# Chess_Clock.net
KiCad netlist of a schematic drawn in Altium Designer
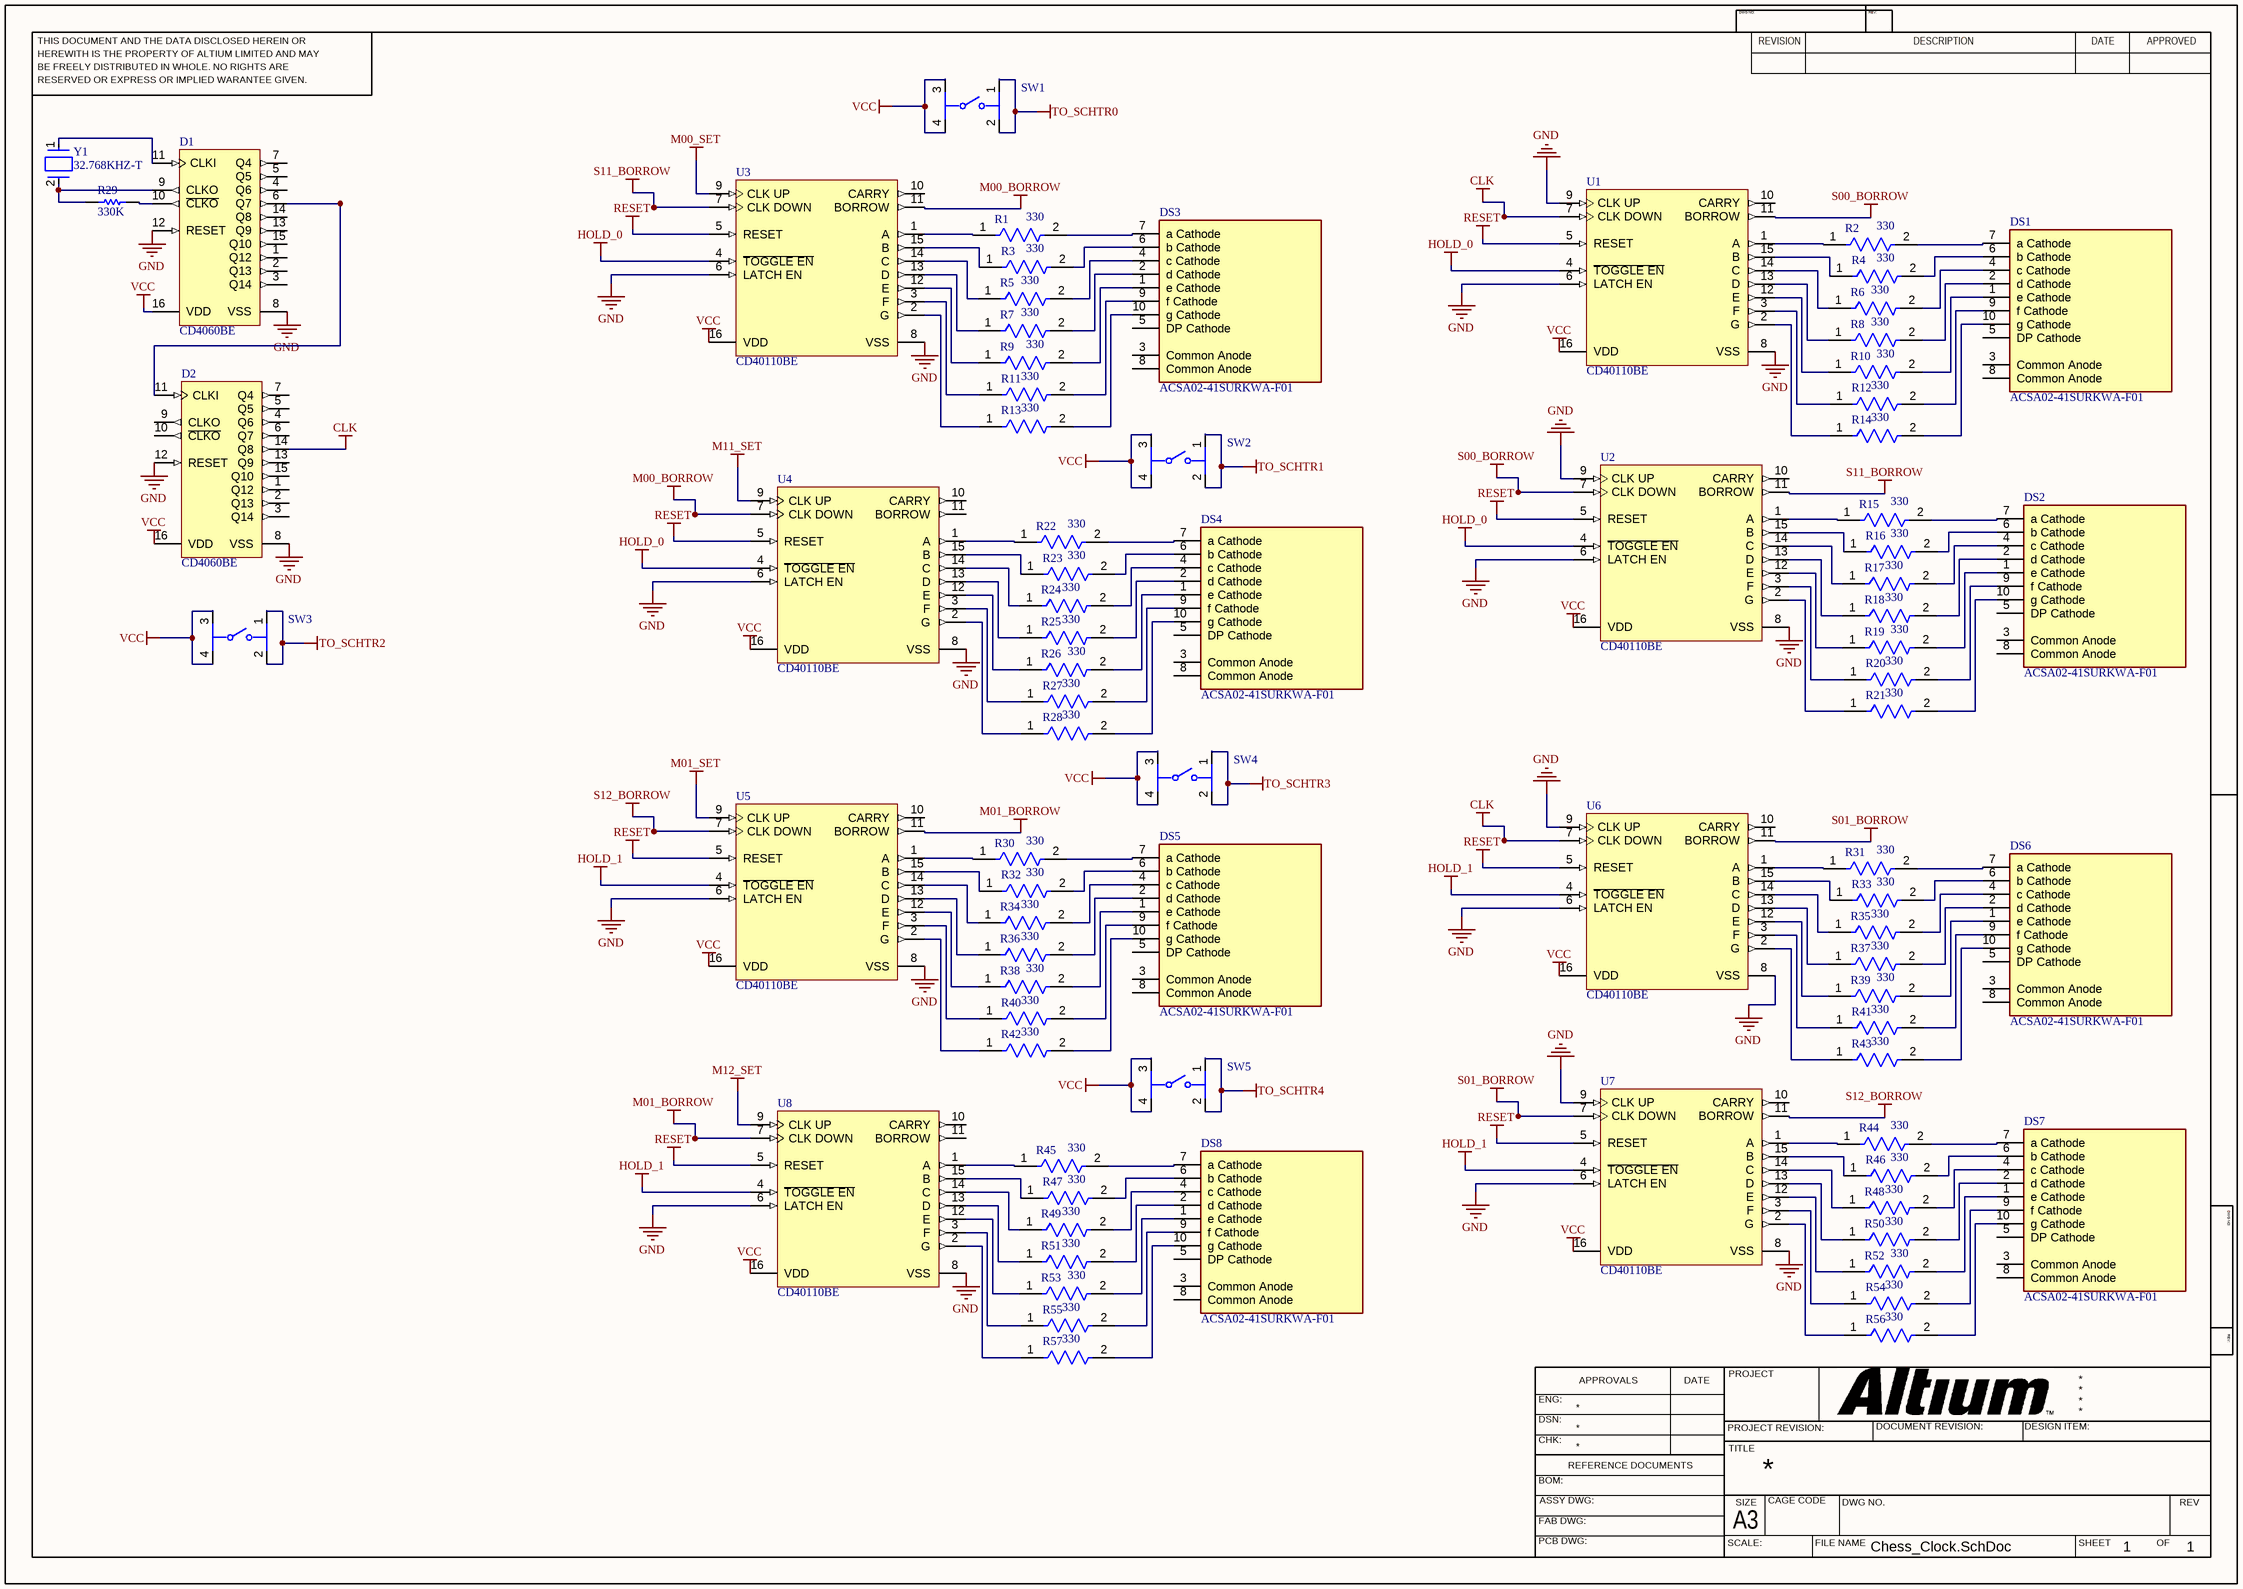
[diagram p0: Chess_Clock.SchDoc]

(export (version "E")
  (design (tool "Eeschema 10.0.6"))
  (components
    (comp (ref "D1")
      (value "CD4060BE")
      (footprint "N0016A")
      (fields (field (name "MANUFACTURER") "Texas Instruments"))
      (libsource (lib "Altium Content Vault") (part "TI-CD4060B-16"))
    )
    (comp (ref "D2")
      (value "CD4060BE")
      (footprint "N0016A")
      (fields (field (name "MANUFACTURER") "Texas Instruments"))
      (libsource (lib "Altium Content Vault") (part "TI-CD4060B-16"))
    )
    (comp (ref "DS1")
      (value "ACSA02-41SURKWA-F01")
      (footprint "FP-ACSA02-41SURKWA-F01-MFG")
      (description "DISPLAY 7-SEG 0.2\" SGL RED 10SMD")
      (libsource (lib "Altium Content Vault") (part "4bb9e92f745044eccd54b42966cc4de"))
    )
    (comp (ref "DS2")
      (value "ACSA02-41SURKWA-F01")
      (footprint "FP-ACSA02-41SURKWA-F01-MFG")
      (description "DISPLAY 7-SEG 0.2\" SGL RED 10SMD")
      (libsource (lib "Altium Content Vault") (part "4bb9e92f745044eccd54b42966cc4de"))
    )
    (comp (ref "DS3")
      (value "ACSA02-41SURKWA-F01")
      (footprint "FP-ACSA02-41SURKWA-F01-MFG")
      (description "DISPLAY 7-SEG 0.2\" SGL RED 10SMD")
      (libsource (lib "Altium Content Vault") (part "4bb9e92f745044eccd54b42966cc4de"))
    )
    (comp (ref "DS4")
      (value "ACSA02-41SURKWA-F01")
      (footprint "FP-ACSA02-41SURKWA-F01-MFG")
      (description "DISPLAY 7-SEG 0.2\" SGL RED 10SMD")
      (libsource (lib "Altium Content Vault") (part "4bb9e92f745044eccd54b42966cc4de"))
    )
    (comp (ref "DS5")
      (value "ACSA02-41SURKWA-F01")
      (footprint "FP-ACSA02-41SURKWA-F01-MFG")
      (description "DISPLAY 7-SEG 0.2\" SGL RED 10SMD")
      (libsource (lib "Altium Content Vault") (part "4bb9e92f745044eccd54b42966cc4de"))
    )
    (comp (ref "DS6")
      (value "ACSA02-41SURKWA-F01")
      (footprint "FP-ACSA02-41SURKWA-F01-MFG")
      (description "DISPLAY 7-SEG 0.2\" SGL RED 10SMD")
      (libsource (lib "Altium Content Vault") (part "4bb9e92f745044eccd54b42966cc4de"))
    )
    (comp (ref "DS7")
      (value "ACSA02-41SURKWA-F01")
      (footprint "FP-ACSA02-41SURKWA-F01-MFG")
      (description "DISPLAY 7-SEG 0.2\" SGL RED 10SMD")
      (libsource (lib "Altium Content Vault") (part "4bb9e92f745044eccd54b42966cc4de"))
    )
    (comp (ref "DS8")
      (value "ACSA02-41SURKWA-F01")
      (footprint "FP-ACSA02-41SURKWA-F01-MFG")
      (description "DISPLAY 7-SEG 0.2\" SGL RED 10SMD")
      (libsource (lib "Altium Content Vault") (part "4bb9e92f745044eccd54b42966cc4de"))
    )
    (comp (ref "R1")
      (value "330")
      (footprint "FP-CRCW0603-e3-MFG")
      (description "RES Thick Film, 330Ω, 1%, 0.1W, 100ppm/°C, 0603")
      (fields (field (name "TOLERANCE") "1%"))
      (libsource (lib "Altium Content Vault") (part "1029c3af85768c4190bb7ad29bc67b5"))
    )
    (comp (ref "R2")
      (value "330")
      (footprint "FP-CRCW0603-e3-MFG")
      (description "RES Thick Film, 330Ω, 1%, 0.1W, 100ppm/°C, 0603")
      (fields (field (name "TOLERANCE") "1%"))
      (libsource (lib "Altium Content Vault") (part "1029c3af85768c4190bb7ad29bc67b5"))
    )
    (comp (ref "R3")
      (value "330")
      (footprint "FP-CRCW0603-e3-MFG")
      (description "RES Thick Film, 330Ω, 1%, 0.1W, 100ppm/°C, 0603")
      (fields (field (name "TOLERANCE") "1%"))
      (libsource (lib "Altium Content Vault") (part "1029c3af85768c4190bb7ad29bc67b5"))
    )
    (comp (ref "R4")
      (value "330")
      (footprint "FP-CRCW0603-e3-MFG")
      (description "RES Thick Film, 330Ω, 1%, 0.1W, 100ppm/°C, 0603")
      (fields (field (name "TOLERANCE") "1%"))
      (libsource (lib "Altium Content Vault") (part "1029c3af85768c4190bb7ad29bc67b5"))
    )
    (comp (ref "R5")
      (value "330")
      (footprint "FP-CRCW0603-e3-MFG")
      (description "RES Thick Film, 330Ω, 1%, 0.1W, 100ppm/°C, 0603")
      (fields (field (name "TOLERANCE") "1%"))
      (libsource (lib "Altium Content Vault") (part "1029c3af85768c4190bb7ad29bc67b5"))
    )
    (comp (ref "R6")
      (value "330")
      (footprint "FP-CRCW0603-e3-MFG")
      (description "RES Thick Film, 330Ω, 1%, 0.1W, 100ppm/°C, 0603")
      (fields (field (name "TOLERANCE") "1%"))
      (libsource (lib "Altium Content Vault") (part "1029c3af85768c4190bb7ad29bc67b5"))
    )
    (comp (ref "R7")
      (value "330")
      (footprint "FP-CRCW0603-e3-MFG")
      (description "RES Thick Film, 330Ω, 1%, 0.1W, 100ppm/°C, 0603")
      (fields (field (name "TOLERANCE") "1%"))
      (libsource (lib "Altium Content Vault") (part "1029c3af85768c4190bb7ad29bc67b5"))
    )
    (comp (ref "R8")
      (value "330")
      (footprint "FP-CRCW0603-e3-MFG")
      (description "RES Thick Film, 330Ω, 1%, 0.1W, 100ppm/°C, 0603")
      (fields (field (name "TOLERANCE") "1%"))
      (libsource (lib "Altium Content Vault") (part "1029c3af85768c4190bb7ad29bc67b5"))
    )
    (comp (ref "R9")
      (value "330")
      (footprint "FP-CRCW0603-e3-MFG")
      (description "RES Thick Film, 330Ω, 1%, 0.1W, 100ppm/°C, 0603")
      (fields (field (name "TOLERANCE") "1%"))
      (libsource (lib "Altium Content Vault") (part "1029c3af85768c4190bb7ad29bc67b5"))
    )
    (comp (ref "R10")
      (value "330")
      (footprint "FP-CRCW0603-e3-MFG")
      (description "RES Thick Film, 330Ω, 1%, 0.1W, 100ppm/°C, 0603")
      (fields (field (name "TOLERANCE") "1%"))
      (libsource (lib "Altium Content Vault") (part "1029c3af85768c4190bb7ad29bc67b5"))
    )
    (comp (ref "R11")
      (value "330")
      (footprint "FP-CRCW0603-e3-MFG")
      (description "RES Thick Film, 330Ω, 1%, 0.1W, 100ppm/°C, 0603")
      (fields (field (name "TOLERANCE") "1%"))
      (libsource (lib "Altium Content Vault") (part "1029c3af85768c4190bb7ad29bc67b5"))
    )
    (comp (ref "R12")
      (value "330")
      (footprint "FP-CRCW0603-e3-MFG")
      (description "RES Thick Film, 330Ω, 1%, 0.1W, 100ppm/°C, 0603")
      (fields (field (name "TOLERANCE") "1%"))
      (libsource (lib "Altium Content Vault") (part "1029c3af85768c4190bb7ad29bc67b5"))
    )
    (comp (ref "R13")
      (value "330")
      (footprint "FP-CRCW0603-e3-MFG")
      (description "RES Thick Film, 330Ω, 1%, 0.1W, 100ppm/°C, 0603")
      (fields (field (name "TOLERANCE") "1%"))
      (libsource (lib "Altium Content Vault") (part "1029c3af85768c4190bb7ad29bc67b5"))
    )
    (comp (ref "R14")
      (value "330")
      (footprint "FP-CRCW0603-e3-MFG")
      (description "RES Thick Film, 330Ω, 1%, 0.1W, 100ppm/°C, 0603")
      (fields (field (name "TOLERANCE") "1%"))
      (libsource (lib "Altium Content Vault") (part "1029c3af85768c4190bb7ad29bc67b5"))
    )
    (comp (ref "R15")
      (value "330")
      (footprint "FP-CRCW0603-e3-MFG")
      (description "RES Thick Film, 330Ω, 1%, 0.1W, 100ppm/°C, 0603")
      (fields (field (name "TOLERANCE") "1%"))
      (libsource (lib "Altium Content Vault") (part "1029c3af85768c4190bb7ad29bc67b5"))
    )
    (comp (ref "R16")
      (value "330")
      (footprint "FP-CRCW0603-e3-MFG")
      (description "RES Thick Film, 330Ω, 1%, 0.1W, 100ppm/°C, 0603")
      (fields (field (name "TOLERANCE") "1%"))
      (libsource (lib "Altium Content Vault") (part "1029c3af85768c4190bb7ad29bc67b5"))
    )
    (comp (ref "R17")
      (value "330")
      (footprint "FP-CRCW0603-e3-MFG")
      (description "RES Thick Film, 330Ω, 1%, 0.1W, 100ppm/°C, 0603")
      (fields (field (name "TOLERANCE") "1%"))
      (libsource (lib "Altium Content Vault") (part "1029c3af85768c4190bb7ad29bc67b5"))
    )
    (comp (ref "R18")
      (value "330")
      (footprint "FP-CRCW0603-e3-MFG")
      (description "RES Thick Film, 330Ω, 1%, 0.1W, 100ppm/°C, 0603")
      (fields (field (name "TOLERANCE") "1%"))
      (libsource (lib "Altium Content Vault") (part "1029c3af85768c4190bb7ad29bc67b5"))
    )
    (comp (ref "R19")
      (value "330")
      (footprint "FP-CRCW0603-e3-MFG")
      (description "RES Thick Film, 330Ω, 1%, 0.1W, 100ppm/°C, 0603")
      (fields (field (name "TOLERANCE") "1%"))
      (libsource (lib "Altium Content Vault") (part "1029c3af85768c4190bb7ad29bc67b5"))
    )
    (comp (ref "R20")
      (value "330")
      (footprint "FP-CRCW0603-e3-MFG")
      (description "RES Thick Film, 330Ω, 1%, 0.1W, 100ppm/°C, 0603")
      (fields (field (name "TOLERANCE") "1%"))
      (libsource (lib "Altium Content Vault") (part "1029c3af85768c4190bb7ad29bc67b5"))
    )
    (comp (ref "R21")
      (value "330")
      (footprint "FP-CRCW0603-e3-MFG")
      (description "RES Thick Film, 330Ω, 1%, 0.1W, 100ppm/°C, 0603")
      (fields (field (name "TOLERANCE") "1%"))
      (libsource (lib "Altium Content Vault") (part "1029c3af85768c4190bb7ad29bc67b5"))
    )
    (comp (ref "R22")
      (value "330")
      (footprint "FP-CRCW0603-e3-MFG")
      (description "RES Thick Film, 330Ω, 1%, 0.1W, 100ppm/°C, 0603")
      (fields (field (name "TOLERANCE") "1%"))
      (libsource (lib "Altium Content Vault") (part "1029c3af85768c4190bb7ad29bc67b5"))
    )
    (comp (ref "R23")
      (value "330")
      (footprint "FP-CRCW0603-e3-MFG")
      (description "RES Thick Film, 330Ω, 1%, 0.1W, 100ppm/°C, 0603")
      (fields (field (name "TOLERANCE") "1%"))
      (libsource (lib "Altium Content Vault") (part "1029c3af85768c4190bb7ad29bc67b5"))
    )
    (comp (ref "R24")
      (value "330")
      (footprint "FP-CRCW0603-e3-MFG")
      (description "RES Thick Film, 330Ω, 1%, 0.1W, 100ppm/°C, 0603")
      (fields (field (name "TOLERANCE") "1%"))
      (libsource (lib "Altium Content Vault") (part "1029c3af85768c4190bb7ad29bc67b5"))
    )
    (comp (ref "R25")
      (value "330")
      (footprint "FP-CRCW0603-e3-MFG")
      (description "RES Thick Film, 330Ω, 1%, 0.1W, 100ppm/°C, 0603")
      (fields (field (name "TOLERANCE") "1%"))
      (libsource (lib "Altium Content Vault") (part "1029c3af85768c4190bb7ad29bc67b5"))
    )
    (comp (ref "R26")
      (value "330")
      (footprint "FP-CRCW0603-e3-MFG")
      (description "RES Thick Film, 330Ω, 1%, 0.1W, 100ppm/°C, 0603")
      (fields (field (name "TOLERANCE") "1%"))
      (libsource (lib "Altium Content Vault") (part "1029c3af85768c4190bb7ad29bc67b5"))
    )
    (comp (ref "R27")
      (value "330")
      (footprint "FP-CRCW0603-e3-MFG")
      (description "RES Thick Film, 330Ω, 1%, 0.1W, 100ppm/°C, 0603")
      (fields (field (name "TOLERANCE") "1%"))
      (libsource (lib "Altium Content Vault") (part "1029c3af85768c4190bb7ad29bc67b5"))
    )
    (comp (ref "R28")
      (value "330")
      (footprint "FP-CRCW0603-e3-MFG")
      (description "RES Thick Film, 330Ω, 1%, 0.1W, 100ppm/°C, 0603")
      (fields (field (name "TOLERANCE") "1%"))
      (libsource (lib "Altium Content Vault") (part "1029c3af85768c4190bb7ad29bc67b5"))
    )
    (comp (ref "R29")
      (value "330K")
      (footprint "RESC1609X50X30NL8T20")
      (description "Chip Resistor, 0 Ohm, Jumper, 100 mW, -55 to 155 degC, 0603 (1608 Metric), RoHS, Tape and Reel")
      (fields (field (name "MANUFACTURER") "Vishay Semiconductor"))
      (libsource (lib "Altium Content Vault") (part "RES-2"))
    )
    (comp (ref "R30")
      (value "330")
      (footprint "FP-CRCW0603-e3-MFG")
      (description "RES Thick Film, 330Ω, 1%, 0.1W, 100ppm/°C, 0603")
      (fields (field (name "TOLERANCE") "1%"))
      (libsource (lib "Altium Content Vault") (part "1029c3af85768c4190bb7ad29bc67b5"))
    )
    (comp (ref "R31")
      (value "330")
      (footprint "FP-CRCW0603-e3-MFG")
      (description "RES Thick Film, 330Ω, 1%, 0.1W, 100ppm/°C, 0603")
      (fields (field (name "TOLERANCE") "1%"))
      (libsource (lib "Altium Content Vault") (part "1029c3af85768c4190bb7ad29bc67b5"))
    )
    (comp (ref "R32")
      (value "330")
      (footprint "FP-CRCW0603-e3-MFG")
      (description "RES Thick Film, 330Ω, 1%, 0.1W, 100ppm/°C, 0603")
      (fields (field (name "TOLERANCE") "1%"))
      (libsource (lib "Altium Content Vault") (part "1029c3af85768c4190bb7ad29bc67b5"))
    )
    (comp (ref "R33")
      (value "330")
      (footprint "FP-CRCW0603-e3-MFG")
      (description "RES Thick Film, 330Ω, 1%, 0.1W, 100ppm/°C, 0603")
      (fields (field (name "TOLERANCE") "1%"))
      (libsource (lib "Altium Content Vault") (part "1029c3af85768c4190bb7ad29bc67b5"))
    )
    (comp (ref "R34")
      (value "330")
      (footprint "FP-CRCW0603-e3-MFG")
      (description "RES Thick Film, 330Ω, 1%, 0.1W, 100ppm/°C, 0603")
      (fields (field (name "TOLERANCE") "1%"))
      (libsource (lib "Altium Content Vault") (part "1029c3af85768c4190bb7ad29bc67b5"))
    )
    (comp (ref "R35")
      (value "330")
      (footprint "FP-CRCW0603-e3-MFG")
      (description "RES Thick Film, 330Ω, 1%, 0.1W, 100ppm/°C, 0603")
      (fields (field (name "TOLERANCE") "1%"))
      (libsource (lib "Altium Content Vault") (part "1029c3af85768c4190bb7ad29bc67b5"))
    )
    (comp (ref "R36")
      (value "330")
      (footprint "FP-CRCW0603-e3-MFG")
      (description "RES Thick Film, 330Ω, 1%, 0.1W, 100ppm/°C, 0603")
      (fields (field (name "TOLERANCE") "1%"))
      (libsource (lib "Altium Content Vault") (part "1029c3af85768c4190bb7ad29bc67b5"))
    )
    (comp (ref "R37")
      (value "330")
      (footprint "FP-CRCW0603-e3-MFG")
      (description "RES Thick Film, 330Ω, 1%, 0.1W, 100ppm/°C, 0603")
      (fields (field (name "TOLERANCE") "1%"))
      (libsource (lib "Altium Content Vault") (part "1029c3af85768c4190bb7ad29bc67b5"))
    )
    (comp (ref "R38")
      (value "330")
      (footprint "FP-CRCW0603-e3-MFG")
      (description "RES Thick Film, 330Ω, 1%, 0.1W, 100ppm/°C, 0603")
      (fields (field (name "TOLERANCE") "1%"))
      (libsource (lib "Altium Content Vault") (part "1029c3af85768c4190bb7ad29bc67b5"))
    )
    (comp (ref "R39")
      (value "330")
      (footprint "FP-CRCW0603-e3-MFG")
      (description "RES Thick Film, 330Ω, 1%, 0.1W, 100ppm/°C, 0603")
      (fields (field (name "TOLERANCE") "1%"))
      (libsource (lib "Altium Content Vault") (part "1029c3af85768c4190bb7ad29bc67b5"))
    )
    (comp (ref "R40")
      (value "330")
      (footprint "FP-CRCW0603-e3-MFG")
      (description "RES Thick Film, 330Ω, 1%, 0.1W, 100ppm/°C, 0603")
      (fields (field (name "TOLERANCE") "1%"))
      (libsource (lib "Altium Content Vault") (part "1029c3af85768c4190bb7ad29bc67b5"))
    )
    (comp (ref "R41")
      (value "330")
      (footprint "FP-CRCW0603-e3-MFG")
      (description "RES Thick Film, 330Ω, 1%, 0.1W, 100ppm/°C, 0603")
      (fields (field (name "TOLERANCE") "1%"))
      (libsource (lib "Altium Content Vault") (part "1029c3af85768c4190bb7ad29bc67b5"))
    )
    (comp (ref "R42")
      (value "330")
      (footprint "FP-CRCW0603-e3-MFG")
      (description "RES Thick Film, 330Ω, 1%, 0.1W, 100ppm/°C, 0603")
      (fields (field (name "TOLERANCE") "1%"))
      (libsource (lib "Altium Content Vault") (part "1029c3af85768c4190bb7ad29bc67b5"))
    )
    (comp (ref "R43")
      (value "330")
      (footprint "FP-CRCW0603-e3-MFG")
      (description "RES Thick Film, 330Ω, 1%, 0.1W, 100ppm/°C, 0603")
      (fields (field (name "TOLERANCE") "1%"))
      (libsource (lib "Altium Content Vault") (part "1029c3af85768c4190bb7ad29bc67b5"))
    )
    (comp (ref "R44")
      (value "330")
      (footprint "FP-CRCW0603-e3-MFG")
      (description "RES Thick Film, 330Ω, 1%, 0.1W, 100ppm/°C, 0603")
      (fields (field (name "TOLERANCE") "1%"))
      (libsource (lib "Altium Content Vault") (part "1029c3af85768c4190bb7ad29bc67b5"))
    )
    (comp (ref "R45")
      (value "330")
      (footprint "FP-CRCW0603-e3-MFG")
      (description "RES Thick Film, 330Ω, 1%, 0.1W, 100ppm/°C, 0603")
      (fields (field (name "TOLERANCE") "1%"))
      (libsource (lib "Altium Content Vault") (part "1029c3af85768c4190bb7ad29bc67b5"))
    )
    (comp (ref "R46")
      (value "330")
      (footprint "FP-CRCW0603-e3-MFG")
      (description "RES Thick Film, 330Ω, 1%, 0.1W, 100ppm/°C, 0603")
      (fields (field (name "TOLERANCE") "1%"))
      (libsource (lib "Altium Content Vault") (part "1029c3af85768c4190bb7ad29bc67b5"))
    )
    (comp (ref "R47")
      (value "330")
      (footprint "FP-CRCW0603-e3-MFG")
      (description "RES Thick Film, 330Ω, 1%, 0.1W, 100ppm/°C, 0603")
      (fields (field (name "TOLERANCE") "1%"))
      (libsource (lib "Altium Content Vault") (part "1029c3af85768c4190bb7ad29bc67b5"))
    )
    (comp (ref "R48")
      (value "330")
      (footprint "FP-CRCW0603-e3-MFG")
      (description "RES Thick Film, 330Ω, 1%, 0.1W, 100ppm/°C, 0603")
      (fields (field (name "TOLERANCE") "1%"))
      (libsource (lib "Altium Content Vault") (part "1029c3af85768c4190bb7ad29bc67b5"))
    )
    (comp (ref "R49")
      (value "330")
      (footprint "FP-CRCW0603-e3-MFG")
      (description "RES Thick Film, 330Ω, 1%, 0.1W, 100ppm/°C, 0603")
      (fields (field (name "TOLERANCE") "1%"))
      (libsource (lib "Altium Content Vault") (part "1029c3af85768c4190bb7ad29bc67b5"))
    )
    (comp (ref "R50")
      (value "330")
      (footprint "FP-CRCW0603-e3-MFG")
      (description "RES Thick Film, 330Ω, 1%, 0.1W, 100ppm/°C, 0603")
      (fields (field (name "TOLERANCE") "1%"))
      (libsource (lib "Altium Content Vault") (part "1029c3af85768c4190bb7ad29bc67b5"))
    )
    (comp (ref "R51")
      (value "330")
      (footprint "FP-CRCW0603-e3-MFG")
      (description "RES Thick Film, 330Ω, 1%, 0.1W, 100ppm/°C, 0603")
      (fields (field (name "TOLERANCE") "1%"))
      (libsource (lib "Altium Content Vault") (part "1029c3af85768c4190bb7ad29bc67b5"))
    )
    (comp (ref "R52")
      (value "330")
      (footprint "FP-CRCW0603-e3-MFG")
      (description "RES Thick Film, 330Ω, 1%, 0.1W, 100ppm/°C, 0603")
      (fields (field (name "TOLERANCE") "1%"))
      (libsource (lib "Altium Content Vault") (part "1029c3af85768c4190bb7ad29bc67b5"))
    )
    (comp (ref "R53")
      (value "330")
      (footprint "FP-CRCW0603-e3-MFG")
      (description "RES Thick Film, 330Ω, 1%, 0.1W, 100ppm/°C, 0603")
      (fields (field (name "TOLERANCE") "1%"))
      (libsource (lib "Altium Content Vault") (part "1029c3af85768c4190bb7ad29bc67b5"))
    )
    (comp (ref "R54")
      (value "330")
      (footprint "FP-CRCW0603-e3-MFG")
      (description "RES Thick Film, 330Ω, 1%, 0.1W, 100ppm/°C, 0603")
      (fields (field (name "TOLERANCE") "1%"))
      (libsource (lib "Altium Content Vault") (part "1029c3af85768c4190bb7ad29bc67b5"))
    )
    (comp (ref "R55")
      (value "330")
      (footprint "FP-CRCW0603-e3-MFG")
      (description "RES Thick Film, 330Ω, 1%, 0.1W, 100ppm/°C, 0603")
      (fields (field (name "TOLERANCE") "1%"))
      (libsource (lib "Altium Content Vault") (part "1029c3af85768c4190bb7ad29bc67b5"))
    )
    (comp (ref "R56")
      (value "330")
      (footprint "FP-CRCW0603-e3-MFG")
      (description "RES Thick Film, 330Ω, 1%, 0.1W, 100ppm/°C, 0603")
      (fields (field (name "TOLERANCE") "1%"))
      (libsource (lib "Altium Content Vault") (part "1029c3af85768c4190bb7ad29bc67b5"))
    )
    (comp (ref "R57")
      (value "330")
      (footprint "FP-CRCW0603-e3-MFG")
      (description "RES Thick Film, 330Ω, 1%, 0.1W, 100ppm/°C, 0603")
      (fields (field (name "TOLERANCE") "1%"))
      (libsource (lib "Altium Content Vault") (part "1029c3af85768c4190bb7ad29bc67b5"))
    )
    (comp (ref "SW1")
      (value "~")
      (footprint "FP-PTS645SM43SMTR92LFS-MFG")
      (description "SWITCH TACTILE SPST-NO 0.05A 12V")
      (libsource (lib "Altium Content Vault") (part "1adf0dd01260c80cf25a44bfd6b99ba"))
    )
    (comp (ref "SW2")
      (value "~")
      (footprint "FP-PTS645SM43SMTR92LFS-MFG")
      (description "SWITCH TACTILE SPST-NO 0.05A 12V")
      (libsource (lib "Altium Content Vault") (part "1adf0dd01260c80cf25a44bfd6b99ba"))
    )
    (comp (ref "SW3")
      (value "~")
      (footprint "FP-PTS645SM43SMTR92LFS-MFG")
      (description "SWITCH TACTILE SPST-NO 0.05A 12V")
      (libsource (lib "Altium Content Vault") (part "1adf0dd01260c80cf25a44bfd6b99ba"))
    )
    (comp (ref "SW4")
      (value "~")
      (footprint "FP-PTS645SM43SMTR92LFS-MFG")
      (description "SWITCH TACTILE SPST-NO 0.05A 12V")
      (libsource (lib "Altium Content Vault") (part "1adf0dd01260c80cf25a44bfd6b99ba"))
    )
    (comp (ref "SW5")
      (value "~")
      (footprint "FP-PTS645SM43SMTR92LFS-MFG")
      (description "SWITCH TACTILE SPST-NO 0.05A 12V")
      (libsource (lib "Altium Content Vault") (part "1adf0dd01260c80cf25a44bfd6b99ba"))
    )
    (comp (ref "U1")
      (value "CD40110BE")
      (footprint "N0016A")
      (description "CMOS Decade Up-Down Counter/Latch/Display Driver, N0016A, TUBE")
      (fields
        (field (name "GENERIC PART NUMBER") "CD40110B")
        (field (name "MANUFACTURER") "Texas Instruments")
      )
      (libsource (lib "Altium Content Vault") (part "TI-CD40110B-N0016A-16"))
    )
    (comp (ref "U2")
      (value "CD40110BE")
      (footprint "N0016A")
      (description "CMOS Decade Up-Down Counter/Latch/Display Driver, N0016A, TUBE")
      (fields
        (field (name "GENERIC PART NUMBER") "CD40110B")
        (field (name "MANUFACTURER") "Texas Instruments")
      )
      (libsource (lib "Altium Content Vault") (part "TI-CD40110B-N0016A-16"))
    )
    (comp (ref "U3")
      (value "CD40110BE")
      (footprint "N0016A")
      (description "CMOS Decade Up-Down Counter/Latch/Display Driver, N0016A, TUBE")
      (fields
        (field (name "GENERIC PART NUMBER") "CD40110B")
        (field (name "MANUFACTURER") "Texas Instruments")
      )
      (libsource (lib "Altium Content Vault") (part "TI-CD40110B-N0016A-16"))
    )
    (comp (ref "U4")
      (value "CD40110BE")
      (footprint "N0016A")
      (description "CMOS Decade Up-Down Counter/Latch/Display Driver, N0016A, TUBE")
      (fields
        (field (name "GENERIC PART NUMBER") "CD40110B")
        (field (name "MANUFACTURER") "Texas Instruments")
      )
      (libsource (lib "Altium Content Vault") (part "TI-CD40110B-N0016A-16"))
    )
    (comp (ref "U5")
      (value "CD40110BE")
      (footprint "N0016A")
      (description "CMOS Decade Up-Down Counter/Latch/Display Driver, N0016A, TUBE")
      (fields
        (field (name "GENERIC PART NUMBER") "CD40110B")
        (field (name "MANUFACTURER") "Texas Instruments")
      )
      (libsource (lib "Altium Content Vault") (part "TI-CD40110B-N0016A-16"))
    )
    (comp (ref "U6")
      (value "CD40110BE")
      (footprint "N0016A")
      (description "CMOS Decade Up-Down Counter/Latch/Display Driver, N0016A, TUBE")
      (fields
        (field (name "GENERIC PART NUMBER") "CD40110B")
        (field (name "MANUFACTURER") "Texas Instruments")
      )
      (libsource (lib "Altium Content Vault") (part "TI-CD40110B-N0016A-16"))
    )
    (comp (ref "U7")
      (value "CD40110BE")
      (footprint "N0016A")
      (description "CMOS Decade Up-Down Counter/Latch/Display Driver, N0016A, TUBE")
      (fields
        (field (name "GENERIC PART NUMBER") "CD40110B")
        (field (name "MANUFACTURER") "Texas Instruments")
      )
      (libsource (lib "Altium Content Vault") (part "TI-CD40110B-N0016A-16"))
    )
    (comp (ref "U8")
      (value "CD40110BE")
      (footprint "N0016A")
      (description "CMOS Decade Up-Down Counter/Latch/Display Driver, N0016A, TUBE")
      (fields
        (field (name "GENERIC PART NUMBER") "CD40110B")
        (field (name "MANUFACTURER") "Texas Instruments")
      )
      (libsource (lib "Altium Content Vault") (part "TI-CD40110B-N0016A-16"))
    )
    (comp (ref "Y1")
      (value "32.768KHZ-T")
      (footprint "FP-AB26TRB-MFG")
      (description "CRYSTAL 32.7680KHZ 12.5PF TH")
      (fields (field (name "TOLERANCE") "20ppm"))
      (libsource (lib "Altium Content Vault") (part "c23a69dc6c9e2f18f2079038eb95dd1"))
    )
  )
  (nets
    (net (code "1") (name "CLK") (class "Default")
      (node (ref "D2") (pin "14") (pinfunction "Q8_14") (pintype "output"))
      (node (ref "U1") (pin "7") (pinfunction "CLK_DOWN_7") (pintype "input"))
      (node (ref "U6") (pin "7") (pinfunction "CLK_DOWN_7") (pintype "input"))
    )
    (net (code "2") (name "GND") (class "Default")
      (node (ref "D1") (pin "12") (pinfunction "RESET_12") (pintype "input"))
      (node (ref "D1") (pin "8") (pinfunction "VSS_8") (pintype "power_in"))
      (node (ref "D2") (pin "12") (pinfunction "RESET_12") (pintype "input"))
      (node (ref "D2") (pin "8") (pinfunction "VSS_8") (pintype "power_in"))
      (node (ref "U1") (pin "6") (pinfunction "LATCH_EN_6") (pintype "input"))
      (node (ref "U1") (pin "8") (pinfunction "VSS_8") (pintype "power_in"))
      (node (ref "U1") (pin "9") (pinfunction "CLK_UP_9") (pintype "input"))
      (node (ref "U2") (pin "6") (pinfunction "LATCH_EN_6") (pintype "input"))
      (node (ref "U2") (pin "8") (pinfunction "VSS_8") (pintype "power_in"))
      (node (ref "U2") (pin "9") (pinfunction "CLK_UP_9") (pintype "input"))
      (node (ref "U3") (pin "6") (pinfunction "LATCH_EN_6") (pintype "input"))
      (node (ref "U3") (pin "8") (pinfunction "VSS_8") (pintype "power_in"))
      (node (ref "U4") (pin "6") (pinfunction "LATCH_EN_6") (pintype "input"))
      (node (ref "U4") (pin "8") (pinfunction "VSS_8") (pintype "power_in"))
      (node (ref "U5") (pin "6") (pinfunction "LATCH_EN_6") (pintype "input"))
      (node (ref "U5") (pin "8") (pinfunction "VSS_8") (pintype "power_in"))
      (node (ref "U6") (pin "6") (pinfunction "LATCH_EN_6") (pintype "input"))
      (node (ref "U6") (pin "8") (pinfunction "VSS_8") (pintype "power_in"))
      (node (ref "U6") (pin "9") (pinfunction "CLK_UP_9") (pintype "input"))
      (node (ref "U7") (pin "6") (pinfunction "LATCH_EN_6") (pintype "input"))
      (node (ref "U7") (pin "8") (pinfunction "VSS_8") (pintype "power_in"))
      (node (ref "U7") (pin "9") (pinfunction "CLK_UP_9") (pintype "input"))
      (node (ref "U8") (pin "6") (pinfunction "LATCH_EN_6") (pintype "input"))
      (node (ref "U8") (pin "8") (pinfunction "VSS_8") (pintype "power_in"))
    )
    (net (code "3") (name "HOLD_0") (class "Default")
      (node (ref "U1") (pin "4") (pinfunction "~{TOGGLE_EN}_4") (pintype "input"))
      (node (ref "U2") (pin "4") (pinfunction "~{TOGGLE_EN}_4") (pintype "input"))
      (node (ref "U3") (pin "4") (pinfunction "~{TOGGLE_EN}_4") (pintype "input"))
      (node (ref "U4") (pin "4") (pinfunction "~{TOGGLE_EN}_4") (pintype "input"))
    )
    (net (code "4") (name "HOLD_1") (class "Default")
      (node (ref "U5") (pin "4") (pinfunction "~{TOGGLE_EN}_4") (pintype "input"))
      (node (ref "U6") (pin "4") (pinfunction "~{TOGGLE_EN}_4") (pintype "input"))
      (node (ref "U7") (pin "4") (pinfunction "~{TOGGLE_EN}_4") (pintype "input"))
      (node (ref "U8") (pin "4") (pinfunction "~{TOGGLE_EN}_4") (pintype "input"))
    )
    (net (code "5") (name "M00_BORROW") (class "Default")
      (node (ref "U3") (pin "11") (pinfunction "BORROW_11") (pintype "output"))
      (node (ref "U4") (pin "7") (pinfunction "CLK_DOWN_7") (pintype "input"))
    )
    (net (code "6") (name "M00_SET") (class "Default")
      (node (ref "U3") (pin "9") (pinfunction "CLK_UP_9") (pintype "input"))
    )
    (net (code "7") (name "M01_BORROW") (class "Default")
      (node (ref "U5") (pin "11") (pinfunction "BORROW_11") (pintype "output"))
      (node (ref "U8") (pin "7") (pinfunction "CLK_DOWN_7") (pintype "input"))
    )
    (net (code "8") (name "M01_SET") (class "Default")
      (node (ref "U5") (pin "9") (pinfunction "CLK_UP_9") (pintype "input"))
    )
    (net (code "9") (name "M11_SET") (class "Default")
      (node (ref "U4") (pin "9") (pinfunction "CLK_UP_9") (pintype "input"))
    )
    (net (code "10") (name "M12_SET") (class "Default")
      (node (ref "U8") (pin "9") (pinfunction "CLK_UP_9") (pintype "input"))
    )
    (net (code "11") (name "Net-(D1-CLKI)") (class "Default")
      (node (ref "D1") (pin "11") (pinfunction "CLKI_11") (pintype "input"))
      (node (ref "Y1") (pin "1") (pinfunction "1_1") (pintype "passive"))
    )
    (net (code "12") (name "Net-(D1-CLKO)") (class "Default")
      (node (ref "D1") (pin "9") (pinfunction "CLKO_9") (pintype "output"))
      (node (ref "R29") (pin "1") (pinfunction "1_1") (pintype "passive"))
      (node (ref "Y1") (pin "2") (pinfunction "2_2") (pintype "passive"))
    )
    (net (code "13") (name "Net-(D1-Q7)") (class "Default")
      (node (ref "D1") (pin "6") (pinfunction "Q7_6") (pintype "output"))
      (node (ref "D2") (pin "11") (pinfunction "CLKI_11") (pintype "input"))
    )
    (net (code "14") (name "Net-(D1-~{CLKO})") (class "Default")
      (node (ref "D1") (pin "10") (pinfunction "~{CLKO}_10") (pintype "output"))
      (node (ref "R29") (pin "2") (pinfunction "2_2") (pintype "passive"))
    )
    (net (code "15") (name "Net-(DS1-a_Cathode)") (class "Default")
      (node (ref "DS1") (pin "7") (pinfunction "a_Cathode_7") (pintype "passive"))
      (node (ref "R2") (pin "2") (pinfunction "2_2") (pintype "passive"))
    )
    (net (code "16") (name "Net-(DS1-b_Cathode)") (class "Default")
      (node (ref "DS1") (pin "6") (pinfunction "b_Cathode_6") (pintype "passive"))
      (node (ref "R4") (pin "2") (pinfunction "2_2") (pintype "passive"))
    )
    (net (code "17") (name "Net-(DS1-c_Cathode)") (class "Default")
      (node (ref "DS1") (pin "4") (pinfunction "c_Cathode_4") (pintype "passive"))
      (node (ref "R6") (pin "2") (pinfunction "2_2") (pintype "passive"))
    )
    (net (code "18") (name "Net-(DS1-d_Cathode)") (class "Default")
      (node (ref "DS1") (pin "2") (pinfunction "d_Cathode_2") (pintype "passive"))
      (node (ref "R8") (pin "2") (pinfunction "2_2") (pintype "passive"))
    )
    (net (code "19") (name "Net-(DS1-e_Cathode)") (class "Default")
      (node (ref "DS1") (pin "1") (pinfunction "e_Cathode_1") (pintype "passive"))
      (node (ref "R10") (pin "2") (pinfunction "2_2") (pintype "passive"))
    )
    (net (code "20") (name "Net-(DS1-f_Cathode)") (class "Default")
      (node (ref "DS1") (pin "9") (pinfunction "f_Cathode_9") (pintype "passive"))
      (node (ref "R12") (pin "2") (pinfunction "2_2") (pintype "passive"))
    )
    (net (code "21") (name "Net-(DS1-g_Cathode)") (class "Default")
      (node (ref "DS1") (pin "10") (pinfunction "g_Cathode_10") (pintype "passive"))
      (node (ref "R14") (pin "2") (pinfunction "2_2") (pintype "passive"))
    )
    (net (code "22") (name "Net-(DS2-a_Cathode)") (class "Default")
      (node (ref "DS2") (pin "7") (pinfunction "a_Cathode_7") (pintype "passive"))
      (node (ref "R15") (pin "2") (pinfunction "2_2") (pintype "passive"))
    )
    (net (code "23") (name "Net-(DS2-b_Cathode)") (class "Default")
      (node (ref "DS2") (pin "6") (pinfunction "b_Cathode_6") (pintype "passive"))
      (node (ref "R16") (pin "2") (pinfunction "2_2") (pintype "passive"))
    )
    (net (code "24") (name "Net-(DS2-c_Cathode)") (class "Default")
      (node (ref "DS2") (pin "4") (pinfunction "c_Cathode_4") (pintype "passive"))
      (node (ref "R17") (pin "2") (pinfunction "2_2") (pintype "passive"))
    )
    (net (code "25") (name "Net-(DS2-d_Cathode)") (class "Default")
      (node (ref "DS2") (pin "2") (pinfunction "d_Cathode_2") (pintype "passive"))
      (node (ref "R18") (pin "2") (pinfunction "2_2") (pintype "passive"))
    )
    (net (code "26") (name "Net-(DS2-e_Cathode)") (class "Default")
      (node (ref "DS2") (pin "1") (pinfunction "e_Cathode_1") (pintype "passive"))
      (node (ref "R19") (pin "2") (pinfunction "2_2") (pintype "passive"))
    )
    (net (code "27") (name "Net-(DS2-f_Cathode)") (class "Default")
      (node (ref "DS2") (pin "9") (pinfunction "f_Cathode_9") (pintype "passive"))
      (node (ref "R20") (pin "2") (pinfunction "2_2") (pintype "passive"))
    )
    (net (code "28") (name "Net-(DS2-g_Cathode)") (class "Default")
      (node (ref "DS2") (pin "10") (pinfunction "g_Cathode_10") (pintype "passive"))
      (node (ref "R21") (pin "2") (pinfunction "2_2") (pintype "passive"))
    )
    (net (code "29") (name "Net-(DS3-a_Cathode)") (class "Default")
      (node (ref "DS3") (pin "7") (pinfunction "a_Cathode_7") (pintype "passive"))
      (node (ref "R1") (pin "2") (pinfunction "2_2") (pintype "passive"))
    )
    (net (code "30") (name "Net-(DS3-b_Cathode)") (class "Default")
      (node (ref "DS3") (pin "6") (pinfunction "b_Cathode_6") (pintype "passive"))
      (node (ref "R3") (pin "2") (pinfunction "2_2") (pintype "passive"))
    )
    (net (code "31") (name "Net-(DS3-c_Cathode)") (class "Default")
      (node (ref "DS3") (pin "4") (pinfunction "c_Cathode_4") (pintype "passive"))
      (node (ref "R5") (pin "2") (pinfunction "2_2") (pintype "passive"))
    )
    (net (code "32") (name "Net-(DS3-d_Cathode)") (class "Default")
      (node (ref "DS3") (pin "2") (pinfunction "d_Cathode_2") (pintype "passive"))
      (node (ref "R7") (pin "2") (pinfunction "2_2") (pintype "passive"))
    )
    (net (code "33") (name "Net-(DS3-e_Cathode)") (class "Default")
      (node (ref "DS3") (pin "1") (pinfunction "e_Cathode_1") (pintype "passive"))
      (node (ref "R9") (pin "2") (pinfunction "2_2") (pintype "passive"))
    )
    (net (code "34") (name "Net-(DS3-f_Cathode)") (class "Default")
      (node (ref "DS3") (pin "9") (pinfunction "f_Cathode_9") (pintype "passive"))
      (node (ref "R11") (pin "2") (pinfunction "2_2") (pintype "passive"))
    )
    (net (code "35") (name "Net-(DS3-g_Cathode)") (class "Default")
      (node (ref "DS3") (pin "10") (pinfunction "g_Cathode_10") (pintype "passive"))
      (node (ref "R13") (pin "2") (pinfunction "2_2") (pintype "passive"))
    )
    (net (code "36") (name "Net-(DS4-a_Cathode)") (class "Default")
      (node (ref "DS4") (pin "7") (pinfunction "a_Cathode_7") (pintype "passive"))
      (node (ref "R22") (pin "2") (pinfunction "2_2") (pintype "passive"))
    )
    (net (code "37") (name "Net-(DS4-b_Cathode)") (class "Default")
      (node (ref "DS4") (pin "6") (pinfunction "b_Cathode_6") (pintype "passive"))
      (node (ref "R23") (pin "2") (pinfunction "2_2") (pintype "passive"))
    )
    (net (code "38") (name "Net-(DS4-c_Cathode)") (class "Default")
      (node (ref "DS4") (pin "4") (pinfunction "c_Cathode_4") (pintype "passive"))
      (node (ref "R24") (pin "2") (pinfunction "2_2") (pintype "passive"))
    )
    (net (code "39") (name "Net-(DS4-d_Cathode)") (class "Default")
      (node (ref "DS4") (pin "2") (pinfunction "d_Cathode_2") (pintype "passive"))
      (node (ref "R25") (pin "2") (pinfunction "2_2") (pintype "passive"))
    )
    (net (code "40") (name "Net-(DS4-e_Cathode)") (class "Default")
      (node (ref "DS4") (pin "1") (pinfunction "e_Cathode_1") (pintype "passive"))
      (node (ref "R26") (pin "2") (pinfunction "2_2") (pintype "passive"))
    )
    (net (code "41") (name "Net-(DS4-f_Cathode)") (class "Default")
      (node (ref "DS4") (pin "9") (pinfunction "f_Cathode_9") (pintype "passive"))
      (node (ref "R27") (pin "2") (pinfunction "2_2") (pintype "passive"))
    )
    (net (code "42") (name "Net-(DS4-g_Cathode)") (class "Default")
      (node (ref "DS4") (pin "10") (pinfunction "g_Cathode_10") (pintype "passive"))
      (node (ref "R28") (pin "2") (pinfunction "2_2") (pintype "passive"))
    )
    (net (code "43") (name "Net-(DS5-a_Cathode)") (class "Default")
      (node (ref "DS5") (pin "7") (pinfunction "a_Cathode_7") (pintype "passive"))
      (node (ref "R30") (pin "2") (pinfunction "2_2") (pintype "passive"))
    )
    (net (code "44") (name "Net-(DS5-b_Cathode)") (class "Default")
      (node (ref "DS5") (pin "6") (pinfunction "b_Cathode_6") (pintype "passive"))
      (node (ref "R32") (pin "2") (pinfunction "2_2") (pintype "passive"))
    )
    (net (code "45") (name "Net-(DS5-c_Cathode)") (class "Default")
      (node (ref "DS5") (pin "4") (pinfunction "c_Cathode_4") (pintype "passive"))
      (node (ref "R34") (pin "2") (pinfunction "2_2") (pintype "passive"))
    )
    (net (code "46") (name "Net-(DS5-d_Cathode)") (class "Default")
      (node (ref "DS5") (pin "2") (pinfunction "d_Cathode_2") (pintype "passive"))
      (node (ref "R36") (pin "2") (pinfunction "2_2") (pintype "passive"))
    )
    (net (code "47") (name "Net-(DS5-e_Cathode)") (class "Default")
      (node (ref "DS5") (pin "1") (pinfunction "e_Cathode_1") (pintype "passive"))
      (node (ref "R38") (pin "2") (pinfunction "2_2") (pintype "passive"))
    )
    (net (code "48") (name "Net-(DS5-f_Cathode)") (class "Default")
      (node (ref "DS5") (pin "9") (pinfunction "f_Cathode_9") (pintype "passive"))
      (node (ref "R40") (pin "2") (pinfunction "2_2") (pintype "passive"))
    )
    (net (code "49") (name "Net-(DS5-g_Cathode)") (class "Default")
      (node (ref "DS5") (pin "10") (pinfunction "g_Cathode_10") (pintype "passive"))
      (node (ref "R42") (pin "2") (pinfunction "2_2") (pintype "passive"))
    )
    (net (code "50") (name "Net-(DS6-a_Cathode)") (class "Default")
      (node (ref "DS6") (pin "7") (pinfunction "a_Cathode_7") (pintype "passive"))
      (node (ref "R31") (pin "2") (pinfunction "2_2") (pintype "passive"))
    )
    (net (code "51") (name "Net-(DS6-b_Cathode)") (class "Default")
      (node (ref "DS6") (pin "6") (pinfunction "b_Cathode_6") (pintype "passive"))
      (node (ref "R33") (pin "2") (pinfunction "2_2") (pintype "passive"))
    )
    (net (code "52") (name "Net-(DS6-c_Cathode)") (class "Default")
      (node (ref "DS6") (pin "4") (pinfunction "c_Cathode_4") (pintype "passive"))
      (node (ref "R35") (pin "2") (pinfunction "2_2") (pintype "passive"))
    )
    (net (code "53") (name "Net-(DS6-d_Cathode)") (class "Default")
      (node (ref "DS6") (pin "2") (pinfunction "d_Cathode_2") (pintype "passive"))
      (node (ref "R37") (pin "2") (pinfunction "2_2") (pintype "passive"))
    )
    (net (code "54") (name "Net-(DS6-e_Cathode)") (class "Default")
      (node (ref "DS6") (pin "1") (pinfunction "e_Cathode_1") (pintype "passive"))
      (node (ref "R39") (pin "2") (pinfunction "2_2") (pintype "passive"))
    )
    (net (code "55") (name "Net-(DS6-f_Cathode)") (class "Default")
      (node (ref "DS6") (pin "9") (pinfunction "f_Cathode_9") (pintype "passive"))
      (node (ref "R41") (pin "2") (pinfunction "2_2") (pintype "passive"))
    )
    (net (code "56") (name "Net-(DS6-g_Cathode)") (class "Default")
      (node (ref "DS6") (pin "10") (pinfunction "g_Cathode_10") (pintype "passive"))
      (node (ref "R43") (pin "2") (pinfunction "2_2") (pintype "passive"))
    )
    (net (code "57") (name "Net-(DS7-a_Cathode)") (class "Default")
      (node (ref "DS7") (pin "7") (pinfunction "a_Cathode_7") (pintype "passive"))
      (node (ref "R44") (pin "2") (pinfunction "2_2") (pintype "passive"))
    )
    (net (code "58") (name "Net-(DS7-b_Cathode)") (class "Default")
      (node (ref "DS7") (pin "6") (pinfunction "b_Cathode_6") (pintype "passive"))
      (node (ref "R46") (pin "2") (pinfunction "2_2") (pintype "passive"))
    )
    (net (code "59") (name "Net-(DS7-c_Cathode)") (class "Default")
      (node (ref "DS7") (pin "4") (pinfunction "c_Cathode_4") (pintype "passive"))
      (node (ref "R48") (pin "2") (pinfunction "2_2") (pintype "passive"))
    )
    (net (code "60") (name "Net-(DS7-d_Cathode)") (class "Default")
      (node (ref "DS7") (pin "2") (pinfunction "d_Cathode_2") (pintype "passive"))
      (node (ref "R50") (pin "2") (pinfunction "2_2") (pintype "passive"))
    )
    (net (code "61") (name "Net-(DS7-e_Cathode)") (class "Default")
      (node (ref "DS7") (pin "1") (pinfunction "e_Cathode_1") (pintype "passive"))
      (node (ref "R52") (pin "2") (pinfunction "2_2") (pintype "passive"))
    )
    (net (code "62") (name "Net-(DS7-f_Cathode)") (class "Default")
      (node (ref "DS7") (pin "9") (pinfunction "f_Cathode_9") (pintype "passive"))
      (node (ref "R54") (pin "2") (pinfunction "2_2") (pintype "passive"))
    )
    (net (code "63") (name "Net-(DS7-g_Cathode)") (class "Default")
      (node (ref "DS7") (pin "10") (pinfunction "g_Cathode_10") (pintype "passive"))
      (node (ref "R56") (pin "2") (pinfunction "2_2") (pintype "passive"))
    )
    (net (code "64") (name "Net-(DS8-a_Cathode)") (class "Default")
      (node (ref "DS8") (pin "7") (pinfunction "a_Cathode_7") (pintype "passive"))
      (node (ref "R45") (pin "2") (pinfunction "2_2") (pintype "passive"))
    )
    (net (code "65") (name "Net-(DS8-b_Cathode)") (class "Default")
      (node (ref "DS8") (pin "6") (pinfunction "b_Cathode_6") (pintype "passive"))
      (node (ref "R47") (pin "2") (pinfunction "2_2") (pintype "passive"))
    )
    (net (code "66") (name "Net-(DS8-c_Cathode)") (class "Default")
      (node (ref "DS8") (pin "4") (pinfunction "c_Cathode_4") (pintype "passive"))
      (node (ref "R49") (pin "2") (pinfunction "2_2") (pintype "passive"))
    )
    (net (code "67") (name "Net-(DS8-d_Cathode)") (class "Default")
      (node (ref "DS8") (pin "2") (pinfunction "d_Cathode_2") (pintype "passive"))
      (node (ref "R51") (pin "2") (pinfunction "2_2") (pintype "passive"))
    )
    (net (code "68") (name "Net-(DS8-e_Cathode)") (class "Default")
      (node (ref "DS8") (pin "1") (pinfunction "e_Cathode_1") (pintype "passive"))
      (node (ref "R53") (pin "2") (pinfunction "2_2") (pintype "passive"))
    )
    (net (code "69") (name "Net-(DS8-f_Cathode)") (class "Default")
      (node (ref "DS8") (pin "9") (pinfunction "f_Cathode_9") (pintype "passive"))
      (node (ref "R55") (pin "2") (pinfunction "2_2") (pintype "passive"))
    )
    (net (code "70") (name "Net-(DS8-g_Cathode)") (class "Default")
      (node (ref "DS8") (pin "10") (pinfunction "g_Cathode_10") (pintype "passive"))
      (node (ref "R57") (pin "2") (pinfunction "2_2") (pintype "passive"))
    )
    (net (code "71") (name "Net-(U1-A)") (class "Default")
      (node (ref "R2") (pin "1") (pinfunction "1_1") (pintype "passive"))
      (node (ref "U1") (pin "1") (pinfunction "A_1") (pintype "output"))
    )
    (net (code "72") (name "Net-(U1-B)") (class "Default")
      (node (ref "R4") (pin "1") (pinfunction "1_1") (pintype "passive"))
      (node (ref "U1") (pin "15") (pinfunction "B_15") (pintype "output"))
    )
    (net (code "73") (name "Net-(U1-C)") (class "Default")
      (node (ref "R6") (pin "1") (pinfunction "1_1") (pintype "passive"))
      (node (ref "U1") (pin "14") (pinfunction "C_14") (pintype "output"))
    )
    (net (code "74") (name "Net-(U1-D)") (class "Default")
      (node (ref "R8") (pin "1") (pinfunction "1_1") (pintype "passive"))
      (node (ref "U1") (pin "13") (pinfunction "D_13") (pintype "output"))
    )
    (net (code "75") (name "Net-(U1-E)") (class "Default")
      (node (ref "R10") (pin "1") (pinfunction "1_1") (pintype "passive"))
      (node (ref "U1") (pin "12") (pinfunction "E_12") (pintype "output"))
    )
    (net (code "76") (name "Net-(U1-F)") (class "Default")
      (node (ref "R12") (pin "1") (pinfunction "1_1") (pintype "passive"))
      (node (ref "U1") (pin "3") (pinfunction "F_3") (pintype "output"))
    )
    (net (code "77") (name "Net-(U1-G)") (class "Default")
      (node (ref "R14") (pin "1") (pinfunction "1_1") (pintype "passive"))
      (node (ref "U1") (pin "2") (pinfunction "G_2") (pintype "output"))
    )
    (net (code "78") (name "Net-(U2-A)") (class "Default")
      (node (ref "R15") (pin "1") (pinfunction "1_1") (pintype "passive"))
      (node (ref "U2") (pin "1") (pinfunction "A_1") (pintype "output"))
    )
    (net (code "79") (name "Net-(U2-B)") (class "Default")
      (node (ref "R16") (pin "1") (pinfunction "1_1") (pintype "passive"))
      (node (ref "U2") (pin "15") (pinfunction "B_15") (pintype "output"))
    )
    (net (code "80") (name "Net-(U2-C)") (class "Default")
      (node (ref "R17") (pin "1") (pinfunction "1_1") (pintype "passive"))
      (node (ref "U2") (pin "14") (pinfunction "C_14") (pintype "output"))
    )
    (net (code "81") (name "Net-(U2-D)") (class "Default")
      (node (ref "R18") (pin "1") (pinfunction "1_1") (pintype "passive"))
      (node (ref "U2") (pin "13") (pinfunction "D_13") (pintype "output"))
    )
    (net (code "82") (name "Net-(U2-E)") (class "Default")
      (node (ref "R19") (pin "1") (pinfunction "1_1") (pintype "passive"))
      (node (ref "U2") (pin "12") (pinfunction "E_12") (pintype "output"))
    )
    (net (code "83") (name "Net-(U2-F)") (class "Default")
      (node (ref "R20") (pin "1") (pinfunction "1_1") (pintype "passive"))
      (node (ref "U2") (pin "3") (pinfunction "F_3") (pintype "output"))
    )
    (net (code "84") (name "Net-(U2-G)") (class "Default")
      (node (ref "R21") (pin "1") (pinfunction "1_1") (pintype "passive"))
      (node (ref "U2") (pin "2") (pinfunction "G_2") (pintype "output"))
    )
    (net (code "85") (name "Net-(U3-A)") (class "Default")
      (node (ref "R1") (pin "1") (pinfunction "1_1") (pintype "passive"))
      (node (ref "U3") (pin "1") (pinfunction "A_1") (pintype "output"))
    )
    (net (code "86") (name "Net-(U3-B)") (class "Default")
      (node (ref "R3") (pin "1") (pinfunction "1_1") (pintype "passive"))
      (node (ref "U3") (pin "15") (pinfunction "B_15") (pintype "output"))
    )
    (net (code "87") (name "Net-(U3-C)") (class "Default")
      (node (ref "R5") (pin "1") (pinfunction "1_1") (pintype "passive"))
      (node (ref "U3") (pin "14") (pinfunction "C_14") (pintype "output"))
    )
    (net (code "88") (name "Net-(U3-D)") (class "Default")
      (node (ref "R7") (pin "1") (pinfunction "1_1") (pintype "passive"))
      (node (ref "U3") (pin "13") (pinfunction "D_13") (pintype "output"))
    )
    (net (code "89") (name "Net-(U3-E)") (class "Default")
      (node (ref "R9") (pin "1") (pinfunction "1_1") (pintype "passive"))
      (node (ref "U3") (pin "12") (pinfunction "E_12") (pintype "output"))
    )
    (net (code "90") (name "Net-(U3-F)") (class "Default")
      (node (ref "R11") (pin "1") (pinfunction "1_1") (pintype "passive"))
      (node (ref "U3") (pin "3") (pinfunction "F_3") (pintype "output"))
    )
    (net (code "91") (name "Net-(U3-G)") (class "Default")
      (node (ref "R13") (pin "1") (pinfunction "1_1") (pintype "passive"))
      (node (ref "U3") (pin "2") (pinfunction "G_2") (pintype "output"))
    )
    (net (code "92") (name "Net-(U4-A)") (class "Default")
      (node (ref "R22") (pin "1") (pinfunction "1_1") (pintype "passive"))
      (node (ref "U4") (pin "1") (pinfunction "A_1") (pintype "output"))
    )
    (net (code "93") (name "Net-(U4-B)") (class "Default")
      (node (ref "R23") (pin "1") (pinfunction "1_1") (pintype "passive"))
      (node (ref "U4") (pin "15") (pinfunction "B_15") (pintype "output"))
    )
    (net (code "94") (name "Net-(U4-C)") (class "Default")
      (node (ref "R24") (pin "1") (pinfunction "1_1") (pintype "passive"))
      (node (ref "U4") (pin "14") (pinfunction "C_14") (pintype "output"))
    )
    (net (code "95") (name "Net-(U4-D)") (class "Default")
      (node (ref "R25") (pin "1") (pinfunction "1_1") (pintype "passive"))
      (node (ref "U4") (pin "13") (pinfunction "D_13") (pintype "output"))
    )
    (net (code "96") (name "Net-(U4-E)") (class "Default")
      (node (ref "R26") (pin "1") (pinfunction "1_1") (pintype "passive"))
      (node (ref "U4") (pin "12") (pinfunction "E_12") (pintype "output"))
    )
    (net (code "97") (name "Net-(U4-F)") (class "Default")
      (node (ref "R27") (pin "1") (pinfunction "1_1") (pintype "passive"))
      (node (ref "U4") (pin "3") (pinfunction "F_3") (pintype "output"))
    )
    (net (code "98") (name "Net-(U4-G)") (class "Default")
      (node (ref "R28") (pin "1") (pinfunction "1_1") (pintype "passive"))
      (node (ref "U4") (pin "2") (pinfunction "G_2") (pintype "output"))
    )
    (net (code "99") (name "Net-(U5-A)") (class "Default")
      (node (ref "R30") (pin "1") (pinfunction "1_1") (pintype "passive"))
      (node (ref "U5") (pin "1") (pinfunction "A_1") (pintype "output"))
    )
    (net (code "100") (name "Net-(U5-B)") (class "Default")
      (node (ref "R32") (pin "1") (pinfunction "1_1") (pintype "passive"))
      (node (ref "U5") (pin "15") (pinfunction "B_15") (pintype "output"))
    )
    (net (code "101") (name "Net-(U5-C)") (class "Default")
      (node (ref "R34") (pin "1") (pinfunction "1_1") (pintype "passive"))
      (node (ref "U5") (pin "14") (pinfunction "C_14") (pintype "output"))
    )
    (net (code "102") (name "Net-(U5-D)") (class "Default")
      (node (ref "R36") (pin "1") (pinfunction "1_1") (pintype "passive"))
      (node (ref "U5") (pin "13") (pinfunction "D_13") (pintype "output"))
    )
    (net (code "103") (name "Net-(U5-E)") (class "Default")
      (node (ref "R38") (pin "1") (pinfunction "1_1") (pintype "passive"))
      (node (ref "U5") (pin "12") (pinfunction "E_12") (pintype "output"))
    )
    (net (code "104") (name "Net-(U5-F)") (class "Default")
      (node (ref "R40") (pin "1") (pinfunction "1_1") (pintype "passive"))
      (node (ref "U5") (pin "3") (pinfunction "F_3") (pintype "output"))
    )
    (net (code "105") (name "Net-(U5-G)") (class "Default")
      (node (ref "R42") (pin "1") (pinfunction "1_1") (pintype "passive"))
      (node (ref "U5") (pin "2") (pinfunction "G_2") (pintype "output"))
    )
    (net (code "106") (name "Net-(U6-A)") (class "Default")
      (node (ref "R31") (pin "1") (pinfunction "1_1") (pintype "passive"))
      (node (ref "U6") (pin "1") (pinfunction "A_1") (pintype "output"))
    )
    (net (code "107") (name "Net-(U6-B)") (class "Default")
      (node (ref "R33") (pin "1") (pinfunction "1_1") (pintype "passive"))
      (node (ref "U6") (pin "15") (pinfunction "B_15") (pintype "output"))
    )
    (net (code "108") (name "Net-(U6-C)") (class "Default")
      (node (ref "R35") (pin "1") (pinfunction "1_1") (pintype "passive"))
      (node (ref "U6") (pin "14") (pinfunction "C_14") (pintype "output"))
    )
    (net (code "109") (name "Net-(U6-D)") (class "Default")
      (node (ref "R37") (pin "1") (pinfunction "1_1") (pintype "passive"))
      (node (ref "U6") (pin "13") (pinfunction "D_13") (pintype "output"))
    )
    (net (code "110") (name "Net-(U6-E)") (class "Default")
      (node (ref "R39") (pin "1") (pinfunction "1_1") (pintype "passive"))
      (node (ref "U6") (pin "12") (pinfunction "E_12") (pintype "output"))
    )
    (net (code "111") (name "Net-(U6-F)") (class "Default")
      (node (ref "R41") (pin "1") (pinfunction "1_1") (pintype "passive"))
      (node (ref "U6") (pin "3") (pinfunction "F_3") (pintype "output"))
    )
    (net (code "112") (name "Net-(U6-G)") (class "Default")
      (node (ref "R43") (pin "1") (pinfunction "1_1") (pintype "passive"))
      (node (ref "U6") (pin "2") (pinfunction "G_2") (pintype "output"))
    )
    (net (code "113") (name "Net-(U7-A)") (class "Default")
      (node (ref "R44") (pin "1") (pinfunction "1_1") (pintype "passive"))
      (node (ref "U7") (pin "1") (pinfunction "A_1") (pintype "output"))
    )
    (net (code "114") (name "Net-(U7-B)") (class "Default")
      (node (ref "R46") (pin "1") (pinfunction "1_1") (pintype "passive"))
      (node (ref "U7") (pin "15") (pinfunction "B_15") (pintype "output"))
    )
    (net (code "115") (name "Net-(U7-C)") (class "Default")
      (node (ref "R48") (pin "1") (pinfunction "1_1") (pintype "passive"))
      (node (ref "U7") (pin "14") (pinfunction "C_14") (pintype "output"))
    )
    (net (code "116") (name "Net-(U7-D)") (class "Default")
      (node (ref "R50") (pin "1") (pinfunction "1_1") (pintype "passive"))
      (node (ref "U7") (pin "13") (pinfunction "D_13") (pintype "output"))
    )
    (net (code "117") (name "Net-(U7-E)") (class "Default")
      (node (ref "R52") (pin "1") (pinfunction "1_1") (pintype "passive"))
      (node (ref "U7") (pin "12") (pinfunction "E_12") (pintype "output"))
    )
    (net (code "118") (name "Net-(U7-F)") (class "Default")
      (node (ref "R54") (pin "1") (pinfunction "1_1") (pintype "passive"))
      (node (ref "U7") (pin "3") (pinfunction "F_3") (pintype "output"))
    )
    (net (code "119") (name "Net-(U7-G)") (class "Default")
      (node (ref "R56") (pin "1") (pinfunction "1_1") (pintype "passive"))
      (node (ref "U7") (pin "2") (pinfunction "G_2") (pintype "output"))
    )
    (net (code "120") (name "Net-(U8-A)") (class "Default")
      (node (ref "R45") (pin "1") (pinfunction "1_1") (pintype "passive"))
      (node (ref "U8") (pin "1") (pinfunction "A_1") (pintype "output"))
    )
    (net (code "121") (name "Net-(U8-B)") (class "Default")
      (node (ref "R47") (pin "1") (pinfunction "1_1") (pintype "passive"))
      (node (ref "U8") (pin "15") (pinfunction "B_15") (pintype "output"))
    )
    (net (code "122") (name "Net-(U8-C)") (class "Default")
      (node (ref "R49") (pin "1") (pinfunction "1_1") (pintype "passive"))
      (node (ref "U8") (pin "14") (pinfunction "C_14") (pintype "output"))
    )
    (net (code "123") (name "Net-(U8-D)") (class "Default")
      (node (ref "R51") (pin "1") (pinfunction "1_1") (pintype "passive"))
      (node (ref "U8") (pin "13") (pinfunction "D_13") (pintype "output"))
    )
    (net (code "124") (name "Net-(U8-E)") (class "Default")
      (node (ref "R53") (pin "1") (pinfunction "1_1") (pintype "passive"))
      (node (ref "U8") (pin "12") (pinfunction "E_12") (pintype "output"))
    )
    (net (code "125") (name "Net-(U8-F)") (class "Default")
      (node (ref "R55") (pin "1") (pinfunction "1_1") (pintype "passive"))
      (node (ref "U8") (pin "3") (pinfunction "F_3") (pintype "output"))
    )
    (net (code "126") (name "Net-(U8-G)") (class "Default")
      (node (ref "R57") (pin "1") (pinfunction "1_1") (pintype "passive"))
      (node (ref "U8") (pin "2") (pinfunction "G_2") (pintype "output"))
    )
    (net (code "127") (name "RESET") (class "Default")
      (node (ref "U1") (pin "5") (pinfunction "RESET_5") (pintype "input"))
      (node (ref "U2") (pin "5") (pinfunction "RESET_5") (pintype "input"))
      (node (ref "U3") (pin "5") (pinfunction "RESET_5") (pintype "input"))
      (node (ref "U4") (pin "5") (pinfunction "RESET_5") (pintype "input"))
      (node (ref "U5") (pin "5") (pinfunction "RESET_5") (pintype "input"))
      (node (ref "U6") (pin "5") (pinfunction "RESET_5") (pintype "input"))
      (node (ref "U7") (pin "5") (pinfunction "RESET_5") (pintype "input"))
      (node (ref "U8") (pin "5") (pinfunction "RESET_5") (pintype "input"))
    )
    (net (code "128") (name "S00_BORROW") (class "Default")
      (node (ref "U1") (pin "11") (pinfunction "BORROW_11") (pintype "output"))
      (node (ref "U2") (pin "7") (pinfunction "CLK_DOWN_7") (pintype "input"))
    )
    (net (code "129") (name "S01_BORROW") (class "Default")
      (node (ref "U6") (pin "11") (pinfunction "BORROW_11") (pintype "output"))
      (node (ref "U7") (pin "7") (pinfunction "CLK_DOWN_7") (pintype "input"))
    )
    (net (code "130") (name "S11_BORROW") (class "Default")
      (node (ref "U2") (pin "11") (pinfunction "BORROW_11") (pintype "output"))
      (node (ref "U3") (pin "7") (pinfunction "CLK_DOWN_7") (pintype "input"))
    )
    (net (code "131") (name "S12_BORROW") (class "Default")
      (node (ref "U5") (pin "7") (pinfunction "CLK_DOWN_7") (pintype "input"))
      (node (ref "U7") (pin "11") (pinfunction "BORROW_11") (pintype "output"))
    )
    (net (code "132") (name "TO_SCHTR0") (class "Default")
      (node (ref "SW1") (pin "1") (pinfunction "1_1") (pintype "passive"))
      (node (ref "SW1") (pin "2") (pinfunction "2_2") (pintype "passive"))
    )
    (net (code "133") (name "TO_SCHTR1") (class "Default")
      (node (ref "SW2") (pin "1") (pinfunction "1_1") (pintype "passive"))
      (node (ref "SW2") (pin "2") (pinfunction "2_2") (pintype "passive"))
    )
    (net (code "134") (name "TO_SCHTR2") (class "Default")
      (node (ref "SW3") (pin "1") (pinfunction "1_1") (pintype "passive"))
      (node (ref "SW3") (pin "2") (pinfunction "2_2") (pintype "passive"))
    )
    (net (code "135") (name "TO_SCHTR3") (class "Default")
      (node (ref "SW4") (pin "1") (pinfunction "1_1") (pintype "passive"))
      (node (ref "SW4") (pin "2") (pinfunction "2_2") (pintype "passive"))
    )
    (net (code "136") (name "TO_SCHTR4") (class "Default")
      (node (ref "SW5") (pin "1") (pinfunction "1_1") (pintype "passive"))
      (node (ref "SW5") (pin "2") (pinfunction "2_2") (pintype "passive"))
    )
    (net (code "137") (name "VCC") (class "Default")
      (node (ref "D1") (pin "16") (pinfunction "VDD_16") (pintype "power_in"))
      (node (ref "D2") (pin "16") (pinfunction "VDD_16") (pintype "power_in"))
      (node (ref "SW1") (pin "3") (pinfunction "3_3") (pintype "passive"))
      (node (ref "SW1") (pin "4") (pinfunction "4_4") (pintype "passive"))
      (node (ref "SW2") (pin "3") (pinfunction "3_3") (pintype "passive"))
      (node (ref "SW2") (pin "4") (pinfunction "4_4") (pintype "passive"))
      (node (ref "SW3") (pin "3") (pinfunction "3_3") (pintype "passive"))
      (node (ref "SW3") (pin "4") (pinfunction "4_4") (pintype "passive"))
      (node (ref "SW4") (pin "3") (pinfunction "3_3") (pintype "passive"))
      (node (ref "SW4") (pin "4") (pinfunction "4_4") (pintype "passive"))
      (node (ref "SW5") (pin "3") (pinfunction "3_3") (pintype "passive"))
      (node (ref "SW5") (pin "4") (pinfunction "4_4") (pintype "passive"))
      (node (ref "U1") (pin "16") (pinfunction "VDD_16") (pintype "power_in"))
      (node (ref "U2") (pin "16") (pinfunction "VDD_16") (pintype "power_in"))
      (node (ref "U3") (pin "16") (pinfunction "VDD_16") (pintype "power_in"))
      (node (ref "U4") (pin "16") (pinfunction "VDD_16") (pintype "power_in"))
      (node (ref "U5") (pin "16") (pinfunction "VDD_16") (pintype "power_in"))
      (node (ref "U6") (pin "16") (pinfunction "VDD_16") (pintype "power_in"))
      (node (ref "U7") (pin "16") (pinfunction "VDD_16") (pintype "power_in"))
      (node (ref "U8") (pin "16") (pinfunction "VDD_16") (pintype "power_in"))
    )
    (net (code "138") (name "unconnected-(D1-Q4-Pad7)") (class "Default")
      (node (ref "D1") (pin "7") (pinfunction "Q4_7") (pintype "output"))
    )
    (net (code "139") (name "unconnected-(D1-Q5-Pad5)") (class "Default")
      (node (ref "D1") (pin "5") (pinfunction "Q5_5") (pintype "output"))
    )
    (net (code "140") (name "unconnected-(D1-Q6-Pad4)") (class "Default")
      (node (ref "D1") (pin "4") (pinfunction "Q6_4") (pintype "output"))
    )
    (net (code "141") (name "unconnected-(D1-Q8-Pad14)") (class "Default")
      (node (ref "D1") (pin "14") (pinfunction "Q8_14") (pintype "output"))
    )
    (net (code "142") (name "unconnected-(D1-Q9-Pad13)") (class "Default")
      (node (ref "D1") (pin "13") (pinfunction "Q9_13") (pintype "output"))
    )
    (net (code "143") (name "unconnected-(D1-Q10-Pad15)") (class "Default")
      (node (ref "D1") (pin "15") (pinfunction "Q10_15") (pintype "output"))
    )
    (net (code "144") (name "unconnected-(D1-Q12-Pad1)") (class "Default")
      (node (ref "D1") (pin "1") (pinfunction "Q12_1") (pintype "output"))
    )
    (net (code "145") (name "unconnected-(D1-Q13-Pad2)") (class "Default")
      (node (ref "D1") (pin "2") (pinfunction "Q13_2") (pintype "output"))
    )
    (net (code "146") (name "unconnected-(D1-Q14-Pad3)") (class "Default")
      (node (ref "D1") (pin "3") (pinfunction "Q14_3") (pintype "output"))
    )
    (net (code "147") (name "unconnected-(D2-CLKO-Pad9)") (class "Default")
      (node (ref "D2") (pin "9") (pinfunction "CLKO_9") (pintype "output"))
    )
    (net (code "148") (name "unconnected-(D2-Q4-Pad7)") (class "Default")
      (node (ref "D2") (pin "7") (pinfunction "Q4_7") (pintype "output"))
    )
    (net (code "149") (name "unconnected-(D2-Q5-Pad5)") (class "Default")
      (node (ref "D2") (pin "5") (pinfunction "Q5_5") (pintype "output"))
    )
    (net (code "150") (name "unconnected-(D2-Q6-Pad4)") (class "Default")
      (node (ref "D2") (pin "4") (pinfunction "Q6_4") (pintype "output"))
    )
    (net (code "151") (name "unconnected-(D2-Q7-Pad6)") (class "Default")
      (node (ref "D2") (pin "6") (pinfunction "Q7_6") (pintype "output"))
    )
    (net (code "152") (name "unconnected-(D2-Q9-Pad13)") (class "Default")
      (node (ref "D2") (pin "13") (pinfunction "Q9_13") (pintype "output"))
    )
    (net (code "153") (name "unconnected-(D2-Q10-Pad15)") (class "Default")
      (node (ref "D2") (pin "15") (pinfunction "Q10_15") (pintype "output"))
    )
    (net (code "154") (name "unconnected-(D2-Q12-Pad1)") (class "Default")
      (node (ref "D2") (pin "1") (pinfunction "Q12_1") (pintype "output"))
    )
    (net (code "155") (name "unconnected-(D2-Q13-Pad2)") (class "Default")
      (node (ref "D2") (pin "2") (pinfunction "Q13_2") (pintype "output"))
    )
    (net (code "156") (name "unconnected-(D2-Q14-Pad3)") (class "Default")
      (node (ref "D2") (pin "3") (pinfunction "Q14_3") (pintype "output"))
    )
    (net (code "157") (name "unconnected-(D2-~{CLKO}-Pad10)") (class "Default")
      (node (ref "D2") (pin "10") (pinfunction "~{CLKO}_10") (pintype "output"))
    )
    (net (code "158") (name "unconnected-(DS1-Common_Anode-Pad3)") (class "Default")
      (node (ref "DS1") (pin "3") (pinfunction "Common_Anode_3") (pintype "passive"))
    )
    (net (code "159") (name "unconnected-(DS1-Common_Anode-Pad8)") (class "Default")
      (node (ref "DS1") (pin "8") (pinfunction "Common_Anode_8") (pintype "passive"))
    )
    (net (code "160") (name "unconnected-(DS1-DP_Cathode-Pad5)") (class "Default")
      (node (ref "DS1") (pin "5") (pinfunction "DP_Cathode_5") (pintype "passive"))
    )
    (net (code "161") (name "unconnected-(DS2-Common_Anode-Pad3)") (class "Default")
      (node (ref "DS2") (pin "3") (pinfunction "Common_Anode_3") (pintype "passive"))
    )
    (net (code "162") (name "unconnected-(DS2-Common_Anode-Pad8)") (class "Default")
      (node (ref "DS2") (pin "8") (pinfunction "Common_Anode_8") (pintype "passive"))
    )
    (net (code "163") (name "unconnected-(DS2-DP_Cathode-Pad5)") (class "Default")
      (node (ref "DS2") (pin "5") (pinfunction "DP_Cathode_5") (pintype "passive"))
    )
    (net (code "164") (name "unconnected-(DS3-Common_Anode-Pad3)") (class "Default")
      (node (ref "DS3") (pin "3") (pinfunction "Common_Anode_3") (pintype "passive"))
    )
    (net (code "165") (name "unconnected-(DS3-Common_Anode-Pad8)") (class "Default")
      (node (ref "DS3") (pin "8") (pinfunction "Common_Anode_8") (pintype "passive"))
    )
    (net (code "166") (name "unconnected-(DS3-DP_Cathode-Pad5)") (class "Default")
      (node (ref "DS3") (pin "5") (pinfunction "DP_Cathode_5") (pintype "passive"))
    )
    (net (code "167") (name "unconnected-(DS4-Common_Anode-Pad3)") (class "Default")
      (node (ref "DS4") (pin "3") (pinfunction "Common_Anode_3") (pintype "passive"))
    )
    (net (code "168") (name "unconnected-(DS4-Common_Anode-Pad8)") (class "Default")
      (node (ref "DS4") (pin "8") (pinfunction "Common_Anode_8") (pintype "passive"))
    )
    (net (code "169") (name "unconnected-(DS4-DP_Cathode-Pad5)") (class "Default")
      (node (ref "DS4") (pin "5") (pinfunction "DP_Cathode_5") (pintype "passive"))
    )
    (net (code "170") (name "unconnected-(DS5-Common_Anode-Pad3)") (class "Default")
      (node (ref "DS5") (pin "3") (pinfunction "Common_Anode_3") (pintype "passive"))
    )
    (net (code "171") (name "unconnected-(DS5-Common_Anode-Pad8)") (class "Default")
      (node (ref "DS5") (pin "8") (pinfunction "Common_Anode_8") (pintype "passive"))
    )
    (net (code "172") (name "unconnected-(DS5-DP_Cathode-Pad5)") (class "Default")
      (node (ref "DS5") (pin "5") (pinfunction "DP_Cathode_5") (pintype "passive"))
    )
    (net (code "173") (name "unconnected-(DS6-Common_Anode-Pad3)") (class "Default")
      (node (ref "DS6") (pin "3") (pinfunction "Common_Anode_3") (pintype "passive"))
    )
    (net (code "174") (name "unconnected-(DS6-Common_Anode-Pad8)") (class "Default")
      (node (ref "DS6") (pin "8") (pinfunction "Common_Anode_8") (pintype "passive"))
    )
    (net (code "175") (name "unconnected-(DS6-DP_Cathode-Pad5)") (class "Default")
      (node (ref "DS6") (pin "5") (pinfunction "DP_Cathode_5") (pintype "passive"))
    )
    (net (code "176") (name "unconnected-(DS7-Common_Anode-Pad3)") (class "Default")
      (node (ref "DS7") (pin "3") (pinfunction "Common_Anode_3") (pintype "passive"))
    )
    (net (code "177") (name "unconnected-(DS7-Common_Anode-Pad8)") (class "Default")
      (node (ref "DS7") (pin "8") (pinfunction "Common_Anode_8") (pintype "passive"))
    )
    (net (code "178") (name "unconnected-(DS7-DP_Cathode-Pad5)") (class "Default")
      (node (ref "DS7") (pin "5") (pinfunction "DP_Cathode_5") (pintype "passive"))
    )
    (net (code "179") (name "unconnected-(DS8-Common_Anode-Pad3)") (class "Default")
      (node (ref "DS8") (pin "3") (pinfunction "Common_Anode_3") (pintype "passive"))
    )
    (net (code "180") (name "unconnected-(DS8-Common_Anode-Pad8)") (class "Default")
      (node (ref "DS8") (pin "8") (pinfunction "Common_Anode_8") (pintype "passive"))
    )
    (net (code "181") (name "unconnected-(DS8-DP_Cathode-Pad5)") (class "Default")
      (node (ref "DS8") (pin "5") (pinfunction "DP_Cathode_5") (pintype "passive"))
    )
    (net (code "182") (name "unconnected-(U1-CARRY-Pad10)") (class "Default")
      (node (ref "U1") (pin "10") (pinfunction "CARRY_10") (pintype "output"))
    )
    (net (code "183") (name "unconnected-(U2-CARRY-Pad10)") (class "Default")
      (node (ref "U2") (pin "10") (pinfunction "CARRY_10") (pintype "output"))
    )
    (net (code "184") (name "unconnected-(U3-CARRY-Pad10)") (class "Default")
      (node (ref "U3") (pin "10") (pinfunction "CARRY_10") (pintype "output"))
    )
    (net (code "185") (name "unconnected-(U4-BORROW-Pad11)") (class "Default")
      (node (ref "U4") (pin "11") (pinfunction "BORROW_11") (pintype "output"))
    )
    (net (code "186") (name "unconnected-(U4-CARRY-Pad10)") (class "Default")
      (node (ref "U4") (pin "10") (pinfunction "CARRY_10") (pintype "output"))
    )
    (net (code "187") (name "unconnected-(U5-CARRY-Pad10)") (class "Default")
      (node (ref "U5") (pin "10") (pinfunction "CARRY_10") (pintype "output"))
    )
    (net (code "188") (name "unconnected-(U6-CARRY-Pad10)") (class "Default")
      (node (ref "U6") (pin "10") (pinfunction "CARRY_10") (pintype "output"))
    )
    (net (code "189") (name "unconnected-(U7-CARRY-Pad10)") (class "Default")
      (node (ref "U7") (pin "10") (pinfunction "CARRY_10") (pintype "output"))
    )
    (net (code "190") (name "unconnected-(U8-BORROW-Pad11)") (class "Default")
      (node (ref "U8") (pin "11") (pinfunction "BORROW_11") (pintype "output"))
    )
    (net (code "191") (name "unconnected-(U8-CARRY-Pad10)") (class "Default")
      (node (ref "U8") (pin "10") (pinfunction "CARRY_10") (pintype "output"))
    )
  )
)
